# d1-mini-r2.net
KiCad netlist of a schematic drawn in EAGLE
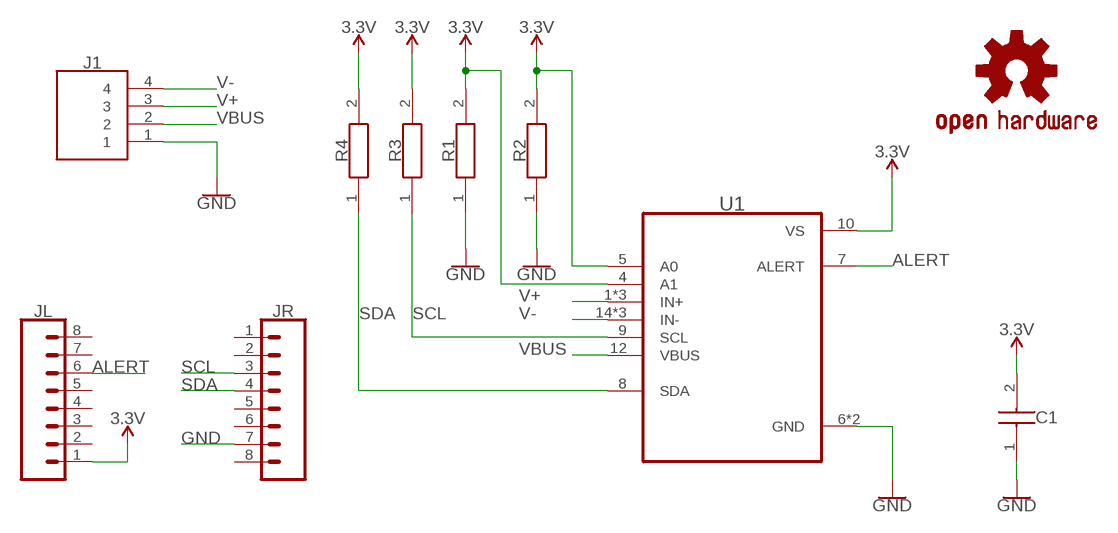
[diagram p0: schematic, sheet 1]

(export (version "E")
  (design (tool "Eeschema 10.0.6"))
  (components
    (comp (ref "C1")
      (value "CL03A105MQ3CSNH")
      (footprint "eagle-import:CAPC1608X80N")
      (libsource (lib "eagle-import") (part "CL03A105MQ3CSNH"))
    )
    (comp (ref "J1")
      (value "282834-4")
      (footprint "eagle-import:2828344")
      (fields (field (name "MOUSER_PART_NUMBER") "571-282834-4"))
      (libsource (lib "eagle-import") (part "282834-4"))
    )
    (comp (ref "JL")
      (value "CONN_08NO_SILK_FEMALE_PTH")
      (footprint "eagle-import:1X08_NO_SILK")
      (libsource (lib "eagle-import") (part "CONN_08NO_SILK_FEMALE_PTH"))
    )
    (comp (ref "JR")
      (value "CONN_08NO_SILK_FEMALE_PTH")
      (footprint "eagle-import:1X08_NO_SILK")
      (libsource (lib "eagle-import") (part "CONN_08NO_SILK_FEMALE_PTH"))
    )
    (comp (ref "LOGO1")
      (value "OSHW-LOGOS")
      (footprint "eagle-import:OSHW-LOGO-S")
      (libsource (lib "eagle-import") (part "OSHW-LOGOS"))
    )
    (comp (ref "R1")
      (value "CRCW020110K0FNED")
      (footprint "eagle-import:RESC0603X28N")
      (fields (field (name "MOUSER_PART_NUMBER") "71-CRCW0201-10K"))
      (libsource (lib "eagle-import") (part "CRCW020110K0FNED"))
    )
    (comp (ref "R2")
      (value "CRCW020110K0FNED")
      (footprint "eagle-import:RESC0603X28N")
      (fields (field (name "MOUSER_PART_NUMBER") "71-CRCW0201-10K"))
      (libsource (lib "eagle-import") (part "CRCW020110K0FNED"))
    )
    (comp (ref "R3")
      (value "CRCW020110K0FNED")
      (footprint "eagle-import:RESC0603X28N")
      (fields (field (name "MOUSER_PART_NUMBER") "71-CRCW0201-10K"))
      (libsource (lib "eagle-import") (part "CRCW020110K0FNED"))
    )
    (comp (ref "R4")
      (value "CRCW020110K0FNED")
      (footprint "eagle-import:RESC0603X28N")
      (fields (field (name "MOUSER_PART_NUMBER") "71-CRCW0201-10K"))
      (libsource (lib "eagle-import") (part "CRCW020110K0FNED"))
    )
    (comp (ref "U1")
      (value "INA260AIPWR")
      (footprint "eagle-import:SOP65P640X120-16N")
      (fields (field (name "MF") "Texas Instruments"))
      (libsource (lib "eagle-import") (part "INA260AIPWR"))
    )
  )
  (nets
    (net (code "1") (name "/ALERT") (class "Default")
      (node (ref "JL") (pin "6") (pinfunction "6_6") (pintype "passive"))
      (node (ref "U1") (pin "7") (pinfunction "ALERT_7") (pintype "output"))
    )
    (net (code "2") (name "/SCL") (class "Default")
      (node (ref "JR") (pin "3") (pinfunction "3_3") (pintype "passive"))
      (node (ref "R3") (pin "1") (pinfunction "1_1") (pintype "bidirectional"))
      (node (ref "U1") (pin "9") (pinfunction "SCL_9") (pintype "input"))
    )
    (net (code "3") (name "/SDA") (class "Default")
      (node (ref "JR") (pin "4") (pinfunction "4_4") (pintype "passive"))
      (node (ref "R4") (pin "1") (pinfunction "1_1") (pintype "bidirectional"))
      (node (ref "U1") (pin "8") (pinfunction "SDA_8") (pintype "bidirectional"))
    )
    (net (code "4") (name "/V+") (class "Default")
      (node (ref "J1") (pin "3") (pinfunction "3_3") (pintype "bidirectional"))
      (node (ref "U1") (pin "1") (pinfunction "IN+_1") (pintype "input"))
      (node (ref "U1") (pin "2") (pinfunction "IN+_2") (pintype "input"))
      (node (ref "U1") (pin "3") (pinfunction "IN+_3") (pintype "input"))
    )
    (net (code "5") (name "/V-") (class "Default")
      (node (ref "J1") (pin "4") (pinfunction "4_4") (pintype "bidirectional"))
      (node (ref "U1") (pin "14") (pinfunction "IN-_14") (pintype "input"))
      (node (ref "U1") (pin "15") (pinfunction "IN-_15") (pintype "input"))
      (node (ref "U1") (pin "16") (pinfunction "IN-_16") (pintype "input"))
    )
    (net (code "6") (name "/VBUS") (class "Default")
      (node (ref "J1") (pin "2") (pinfunction "2_2") (pintype "bidirectional"))
      (node (ref "U1") (pin "12") (pinfunction "VBUS_12") (pintype "input"))
    )
    (net (code "7") (name "3.3V") (class "Default")
      (node (ref "C1") (pin "2") (pinfunction "2_2") (pintype "output"))
      (node (ref "JL") (pin "1") (pinfunction "1_1") (pintype "passive"))
      (node (ref "R1") (pin "2") (pinfunction "2_2") (pintype "bidirectional"))
      (node (ref "R2") (pin "2") (pinfunction "2_2") (pintype "bidirectional"))
      (node (ref "R3") (pin "2") (pinfunction "2_2") (pintype "bidirectional"))
      (node (ref "R4") (pin "2") (pinfunction "2_2") (pintype "bidirectional"))
      (node (ref "U1") (pin "10") (pinfunction "VS_10") (pintype "power_in"))
      (node (ref "U1") (pin "4") (pinfunction "A1_4") (pintype "input"))
      (node (ref "U1") (pin "5") (pinfunction "A0_5") (pintype "input"))
    )
    (net (code "8") (name "GND") (class "Default")
      (node (ref "C1") (pin "1") (pinfunction "1_1") (pintype "input"))
      (node (ref "J1") (pin "1") (pinfunction "1_1") (pintype "bidirectional"))
      (node (ref "JR") (pin "7") (pinfunction "7_7") (pintype "passive"))
      (node (ref "R1") (pin "1") (pinfunction "1_1") (pintype "bidirectional"))
      (node (ref "R2") (pin "1") (pinfunction "1_1") (pintype "bidirectional"))
      (node (ref "U1") (pin "11") (pinfunction "GND_11") (pintype "power_in"))
      (node (ref "U1") (pin "6") (pinfunction "GND_6") (pintype "power_in"))
    )
    (net (code "9") (name "unconnected-(JL-Pad2)") (class "Default")
      (node (ref "JL") (pin "2") (pinfunction "2_2") (pintype "passive"))
    )
    (net (code "10") (name "unconnected-(JL-Pad3)") (class "Default")
      (node (ref "JL") (pin "3") (pinfunction "3_3") (pintype "passive"))
    )
    (net (code "11") (name "unconnected-(JL-Pad4)") (class "Default")
      (node (ref "JL") (pin "4") (pinfunction "4_4") (pintype "passive"))
    )
    (net (code "12") (name "unconnected-(JL-Pad5)") (class "Default")
      (node (ref "JL") (pin "5") (pinfunction "5_5") (pintype "passive"))
    )
    (net (code "13") (name "unconnected-(JL-Pad7)") (class "Default")
      (node (ref "JL") (pin "7") (pinfunction "7_7") (pintype "passive"))
    )
    (net (code "14") (name "unconnected-(JL-Pad8)") (class "Default")
      (node (ref "JL") (pin "8") (pinfunction "8_8") (pintype "passive"))
    )
    (net (code "15") (name "unconnected-(JR-Pad1)") (class "Default")
      (node (ref "JR") (pin "1") (pinfunction "1_1") (pintype "passive"))
    )
    (net (code "16") (name "unconnected-(JR-Pad2)") (class "Default")
      (node (ref "JR") (pin "2") (pinfunction "2_2") (pintype "passive"))
    )
    (net (code "17") (name "unconnected-(JR-Pad5)") (class "Default")
      (node (ref "JR") (pin "5") (pinfunction "5_5") (pintype "passive"))
    )
    (net (code "18") (name "unconnected-(JR-Pad6)") (class "Default")
      (node (ref "JR") (pin "6") (pinfunction "6_6") (pintype "passive"))
    )
    (net (code "19") (name "unconnected-(JR-Pad8)") (class "Default")
      (node (ref "JR") (pin "8") (pinfunction "8_8") (pintype "passive"))
    )
  )
)
